# MainSCH.net
KiCad netlist of a schematic drawn in EAGLE
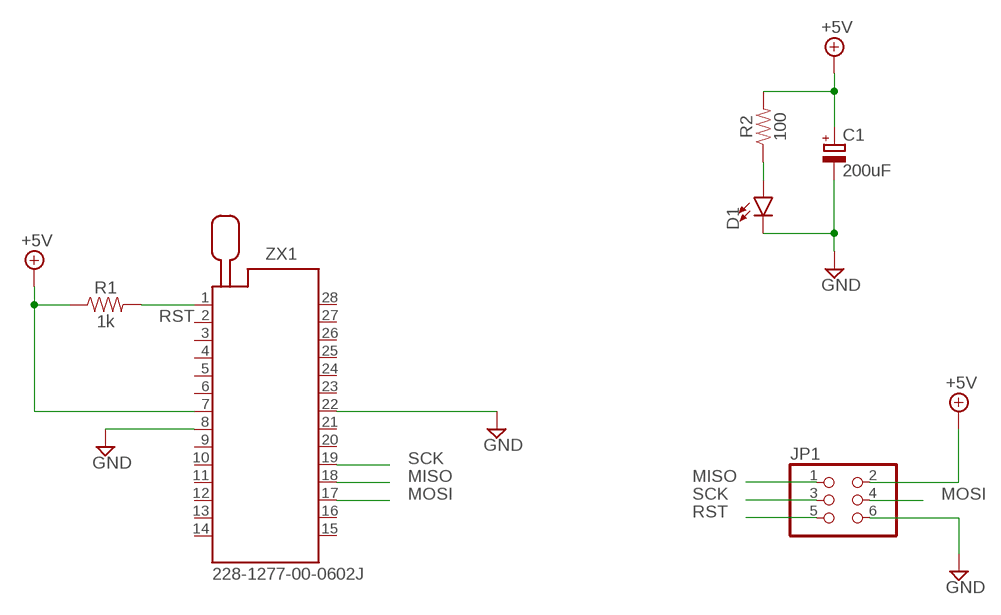
[diagram p0: schematic, sheet 1]

(export (version "E")
  (design (tool "Eeschema 10.0.6"))
  (components
    (comp (ref "C1")
      (value "200uF")
      (footprint "eagle-import:E2,5-6")
      (libsource (lib "eagle-import") (part "CPOL-EUE2.5-6"))
    )
    (comp (ref "D1")
      (value "LED0603")
      (footprint "eagle-import:LED-0603")
      (libsource (lib "eagle-import") (part "LED0603"))
    )
    (comp (ref "JP1")
      (value "PINHD-2X3")
      (footprint "eagle-import:2X03")
      (libsource (lib "eagle-import") (part "PINHD-2X3"))
    )
    (comp (ref "R1")
      (value "1k")
      (footprint "eagle-import:0603")
      (libsource (lib "eagle-import") (part "1KOHM-0603-1/10W-1%"))
    )
    (comp (ref "R2")
      (value "100")
      (footprint "eagle-import:0603")
      (libsource (lib "eagle-import") (part "100OHM-0603-1/10W-1%"))
    )
    (comp (ref "ZX1")
      (value "228-1277-00-0602J")
      (footprint "eagle-import:228-1277-00-0602J")
      (fields (field (name "MF") "3M"))
      (libsource (lib "eagle-import") (part "228-?00-0602J1277-"))
    )
  )
  (nets
    (net (code "1") (name "+5V") (class "Default")
      (node (ref "C1") (pin "+") (pinfunction "+_+") (pintype "passive"))
      (node (ref "JP1") (pin "2") (pinfunction "2_2") (pintype "passive"))
      (node (ref "R1") (pin "1") (pinfunction "1_1") (pintype "passive"))
      (node (ref "R2") (pin "2") (pinfunction "2_2") (pintype "passive"))
      (node (ref "ZX1") (pin "7") (pinfunction "7_7") (pintype "passive"))
    )
    (net (code "2") (name "/MISO") (class "Default")
      (node (ref "JP1") (pin "1") (pinfunction "1_1") (pintype "passive"))
      (node (ref "ZX1") (pin "18") (pinfunction "18_18") (pintype "passive"))
    )
    (net (code "3") (name "/MOSI") (class "Default")
      (node (ref "JP1") (pin "4") (pinfunction "4_4") (pintype "passive"))
      (node (ref "ZX1") (pin "17") (pinfunction "17_17") (pintype "passive"))
    )
    (net (code "4") (name "/RST") (class "Default")
      (node (ref "JP1") (pin "5") (pinfunction "5_5") (pintype "passive"))
      (node (ref "R1") (pin "2") (pinfunction "2_2") (pintype "passive"))
      (node (ref "ZX1") (pin "1") (pinfunction "1_1") (pintype "passive"))
    )
    (net (code "5") (name "/SCK") (class "Default")
      (node (ref "JP1") (pin "3") (pinfunction "3_3") (pintype "passive"))
      (node (ref "ZX1") (pin "19") (pinfunction "19_19") (pintype "passive"))
    )
    (net (code "6") (name "GND") (class "Default")
      (node (ref "C1") (pin "-") (pinfunction "-_-") (pintype "passive"))
      (node (ref "D1") (pin "C") (pinfunction "C_C") (pintype "passive"))
      (node (ref "JP1") (pin "6") (pinfunction "6_6") (pintype "passive"))
      (node (ref "ZX1") (pin "22") (pinfunction "22_22") (pintype "passive"))
      (node (ref "ZX1") (pin "8") (pinfunction "8_8") (pintype "passive"))
    )
    (net (code "7") (name "Net-(D1-PadA)") (class "Default")
      (node (ref "D1") (pin "A") (pinfunction "A_A") (pintype "passive"))
      (node (ref "R2") (pin "1") (pinfunction "1_1") (pintype "passive"))
    )
    (net (code "8") (name "unconnected-(ZX1-Pad2)") (class "Default")
      (node (ref "ZX1") (pin "2") (pinfunction "2_2") (pintype "passive"))
    )
    (net (code "9") (name "unconnected-(ZX1-Pad3)") (class "Default")
      (node (ref "ZX1") (pin "3") (pinfunction "3_3") (pintype "passive"))
    )
    (net (code "10") (name "unconnected-(ZX1-Pad4)") (class "Default")
      (node (ref "ZX1") (pin "4") (pinfunction "4_4") (pintype "passive"))
    )
    (net (code "11") (name "unconnected-(ZX1-Pad5)") (class "Default")
      (node (ref "ZX1") (pin "5") (pinfunction "5_5") (pintype "passive"))
    )
    (net (code "12") (name "unconnected-(ZX1-Pad6)") (class "Default")
      (node (ref "ZX1") (pin "6") (pinfunction "6_6") (pintype "passive"))
    )
    (net (code "13") (name "unconnected-(ZX1-Pad9)") (class "Default")
      (node (ref "ZX1") (pin "9") (pinfunction "9_9") (pintype "passive"))
    )
    (net (code "14") (name "unconnected-(ZX1-Pad10)") (class "Default")
      (node (ref "ZX1") (pin "10") (pinfunction "10_10") (pintype "passive"))
    )
    (net (code "15") (name "unconnected-(ZX1-Pad11)") (class "Default")
      (node (ref "ZX1") (pin "11") (pinfunction "11_11") (pintype "passive"))
    )
    (net (code "16") (name "unconnected-(ZX1-Pad12)") (class "Default")
      (node (ref "ZX1") (pin "12") (pinfunction "12_12") (pintype "passive"))
    )
    (net (code "17") (name "unconnected-(ZX1-Pad13)") (class "Default")
      (node (ref "ZX1") (pin "13") (pinfunction "13_13") (pintype "passive"))
    )
    (net (code "18") (name "unconnected-(ZX1-Pad14)") (class "Default")
      (node (ref "ZX1") (pin "14") (pinfunction "14_14") (pintype "passive"))
    )
    (net (code "19") (name "unconnected-(ZX1-Pad15)") (class "Default")
      (node (ref "ZX1") (pin "15") (pinfunction "15_15") (pintype "passive"))
    )
    (net (code "20") (name "unconnected-(ZX1-Pad16)") (class "Default")
      (node (ref "ZX1") (pin "16") (pinfunction "16_16") (pintype "passive"))
    )
    (net (code "21") (name "unconnected-(ZX1-Pad20)") (class "Default")
      (node (ref "ZX1") (pin "20") (pinfunction "20_20") (pintype "passive"))
    )
    (net (code "22") (name "unconnected-(ZX1-Pad21)") (class "Default")
      (node (ref "ZX1") (pin "21") (pinfunction "21_21") (pintype "passive"))
    )
    (net (code "23") (name "unconnected-(ZX1-Pad23)") (class "Default")
      (node (ref "ZX1") (pin "23") (pinfunction "23_23") (pintype "passive"))
    )
    (net (code "24") (name "unconnected-(ZX1-Pad24)") (class "Default")
      (node (ref "ZX1") (pin "24") (pinfunction "24_24") (pintype "passive"))
    )
    (net (code "25") (name "unconnected-(ZX1-Pad25)") (class "Default")
      (node (ref "ZX1") (pin "25") (pinfunction "25_25") (pintype "passive"))
    )
    (net (code "26") (name "unconnected-(ZX1-Pad26)") (class "Default")
      (node (ref "ZX1") (pin "26") (pinfunction "26_26") (pintype "passive"))
    )
    (net (code "27") (name "unconnected-(ZX1-Pad27)") (class "Default")
      (node (ref "ZX1") (pin "27") (pinfunction "27_27") (pintype "passive"))
    )
    (net (code "28") (name "unconnected-(ZX1-Pad28)") (class "Default")
      (node (ref "ZX1") (pin "28") (pinfunction "28_28") (pintype "passive"))
    )
  )
)
